# 24V_Supply.net
KiCad netlist of a schematic drawn in Altium Designer
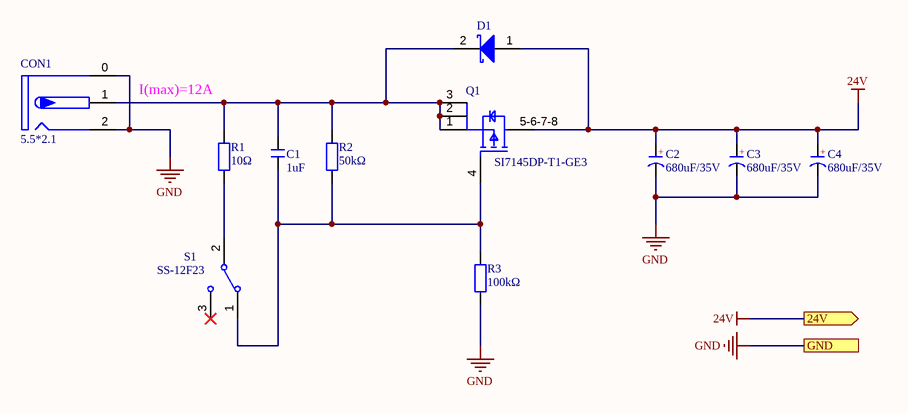
[diagram p0: 24V_Supply.SchDoc]

(export (version "E")
  (design (tool "Eeschema 10.0.6"))
  (components
    (comp (ref "C1")
      (value "1uF")
      (footprint "C 0603_L")
      (description "贴片电容")
      (libsource (lib "0.1 - 电阻-电容-电感") (part "C"))
    )
    (comp (ref "C2")
      (value "680uF/35V")
      (footprint "CM G(12.5*13.5)")
      (description "贴片电解电容")
      (fields (field (name "版权归属") "封装库来自淘宝 ID：黄晶宝石"))
      (libsource (lib "0.1 - 电阻-电容-电感") (part "CE_SMD"))
    )
    (comp (ref "C3")
      (value "680uF/35V")
      (footprint "CM G(12.5*13.5)")
      (description "贴片电解电容")
      (fields (field (name "版权归属") "封装库来自淘宝 ID：黄晶宝石"))
      (libsource (lib "0.1 - 电阻-电容-电感") (part "CE_SMD"))
    )
    (comp (ref "C4")
      (value "680uF/35V")
      (footprint "CM G(12.5*13.5)")
      (description "贴片电解电容")
      (fields (field (name "版权归属") "封装库来自淘宝 ID：黄晶宝石"))
      (libsource (lib "0.1 - 电阻-电容-电感") (part "CE_SMD"))
    )
    (comp (ref "CON1")
      (value "5.5*2.1")
      (footprint "DC-005P")
      (description "带屏蔽DC电源接口\r\n*LCID: C3001296")
      (libsource (lib "0.8 - 以太网-音频-USB插座") (part "DC-005P"))
    )
    (comp (ref "D1")
      (value "B530C-13-F")
      (footprint "DIOD-SMC-2_V")
      (libsource (lib "Altium Content Vault") (part "DSKY-AK-2"))
    )
    (comp (ref "Q1")
      (value "SI7145DP-T1-GE3")
      (footprint "FP-S17-0173-SINGLE-MFG")
      (description "MOSFET P-CH 30V 60A PPAK SO-8\r\n*LCID: C725172")
      (fields
        (field (name "OCTOPART") "https://octopart.com/si7145dp-t1-ge3-vishay-42623172")
        (field (name "MANUFACTURER") "Vishay")
      )
      (libsource (lib "Altium Content Vault") (part "69475525114238b3975de0d3db13512"))
    )
    (comp (ref "R1")
      (value "10Ω")
      (footprint "R 0603_L")
      (description "贴片电阻")
      (fields (field (name "版权归属") "来自淘宝 ID：黄晶宝石"))
      (libsource (lib "0.1 - 电阻-电容-电感") (part "R"))
    )
    (comp (ref "R2")
      (value "50kΩ")
      (footprint "R 0603_L")
      (description "贴片电阻")
      (fields (field (name "版权归属") "来自淘宝 ID：黄晶宝石"))
      (libsource (lib "0.1 - 电阻-电容-电感") (part "R"))
    )
    (comp (ref "R3")
      (value "100kΩ")
      (footprint "R 0603_L")
      (description "贴片电阻")
      (fields (field (name "版权归属") "来自淘宝 ID：黄晶宝石"))
      (libsource (lib "0.1 - 电阻-电容-电感") (part "R"))
    )
    (comp (ref "S1")
      (value "SS-12F23")
      (footprint "SS-SG2")
      (description "1路波动开关\r\n*LCID: C480340")
      (fields (field (name "版权归属") "封装库来自淘宝 ID：黄晶宝石"))
      (libsource (lib "0.7 - 常用按键-开关") (part "SSW-1P"))
    )
  )
  (nets
    (net (code "1") (name "24V") (class "Default")
      (node (ref "C2") (pin "1") (pinfunction "A_1") (pintype "passive"))
      (node (ref "C3") (pin "1") (pinfunction "A_1") (pintype "passive"))
      (node (ref "C4") (pin "1") (pinfunction "A_1") (pintype "passive"))
      (node (ref "D1") (pin "1") (pinfunction "A_1") (pintype "passive"))
      (node (ref "Q1") (pin "5-6-7-8") (pinfunction "D_5-6-7-8") (pintype "passive"))
    )
    (net (code "2") (name "GND") (class "Default")
      (node (ref "C2") (pin "2") (pinfunction "K_2") (pintype "passive"))
      (node (ref "C3") (pin "2") (pinfunction "K_2") (pintype "passive"))
      (node (ref "C4") (pin "2") (pinfunction "K_2") (pintype "passive"))
      (node (ref "CON1") (pin "0") (pintype "passive"))
      (node (ref "CON1") (pin "2") (pintype "power_in"))
      (node (ref "R3") (pin "1") (pinfunction "1_1") (pintype "passive"))
    )
    (net (code "3") (name "Net-(D1-K)") (class "Default")
      (node (ref "C1") (pin "2") (pinfunction "2_2") (pintype "passive"))
      (node (ref "CON1") (pin "1") (pintype "power_in"))
      (node (ref "D1") (pin "2") (pinfunction "K_2") (pintype "passive"))
      (node (ref "Q1") (pin "1") (pinfunction "S_1") (pintype "passive"))
      (node (ref "Q1") (pin "2") (pinfunction "S_2") (pintype "passive"))
      (node (ref "Q1") (pin "3") (pinfunction "S_3") (pintype "passive"))
      (node (ref "R1") (pin "2") (pinfunction "2_2") (pintype "passive"))
      (node (ref "R2") (pin "2") (pinfunction "2_2") (pintype "passive"))
    )
    (net (code "4") (name "Net-(Q1-G)") (class "Default")
      (node (ref "C1") (pin "1") (pinfunction "1_1") (pintype "passive"))
      (node (ref "Q1") (pin "4") (pinfunction "G_4") (pintype "passive"))
      (node (ref "R2") (pin "1") (pinfunction "1_1") (pintype "passive"))
      (node (ref "R3") (pin "2") (pinfunction "2_2") (pintype "passive"))
      (node (ref "S1") (pin "1") (pinfunction "1_1") (pintype "passive"))
    )
    (net (code "5") (name "Net-(R1-Pad1)") (class "Default")
      (node (ref "R1") (pin "1") (pinfunction "1_1") (pintype "passive"))
      (node (ref "S1") (pin "2") (pinfunction "2_2") (pintype "passive"))
    )
    (net (code "6") (name "unconnected-(S1-Pad3)") (class "Default")
      (node (ref "S1") (pin "3") (pinfunction "3_3") (pintype "passive+no_connect"))
    )
  )
)
